# HenHouseControlleri2cfix.net
KiCad netlist of a schematic drawn in EAGLE
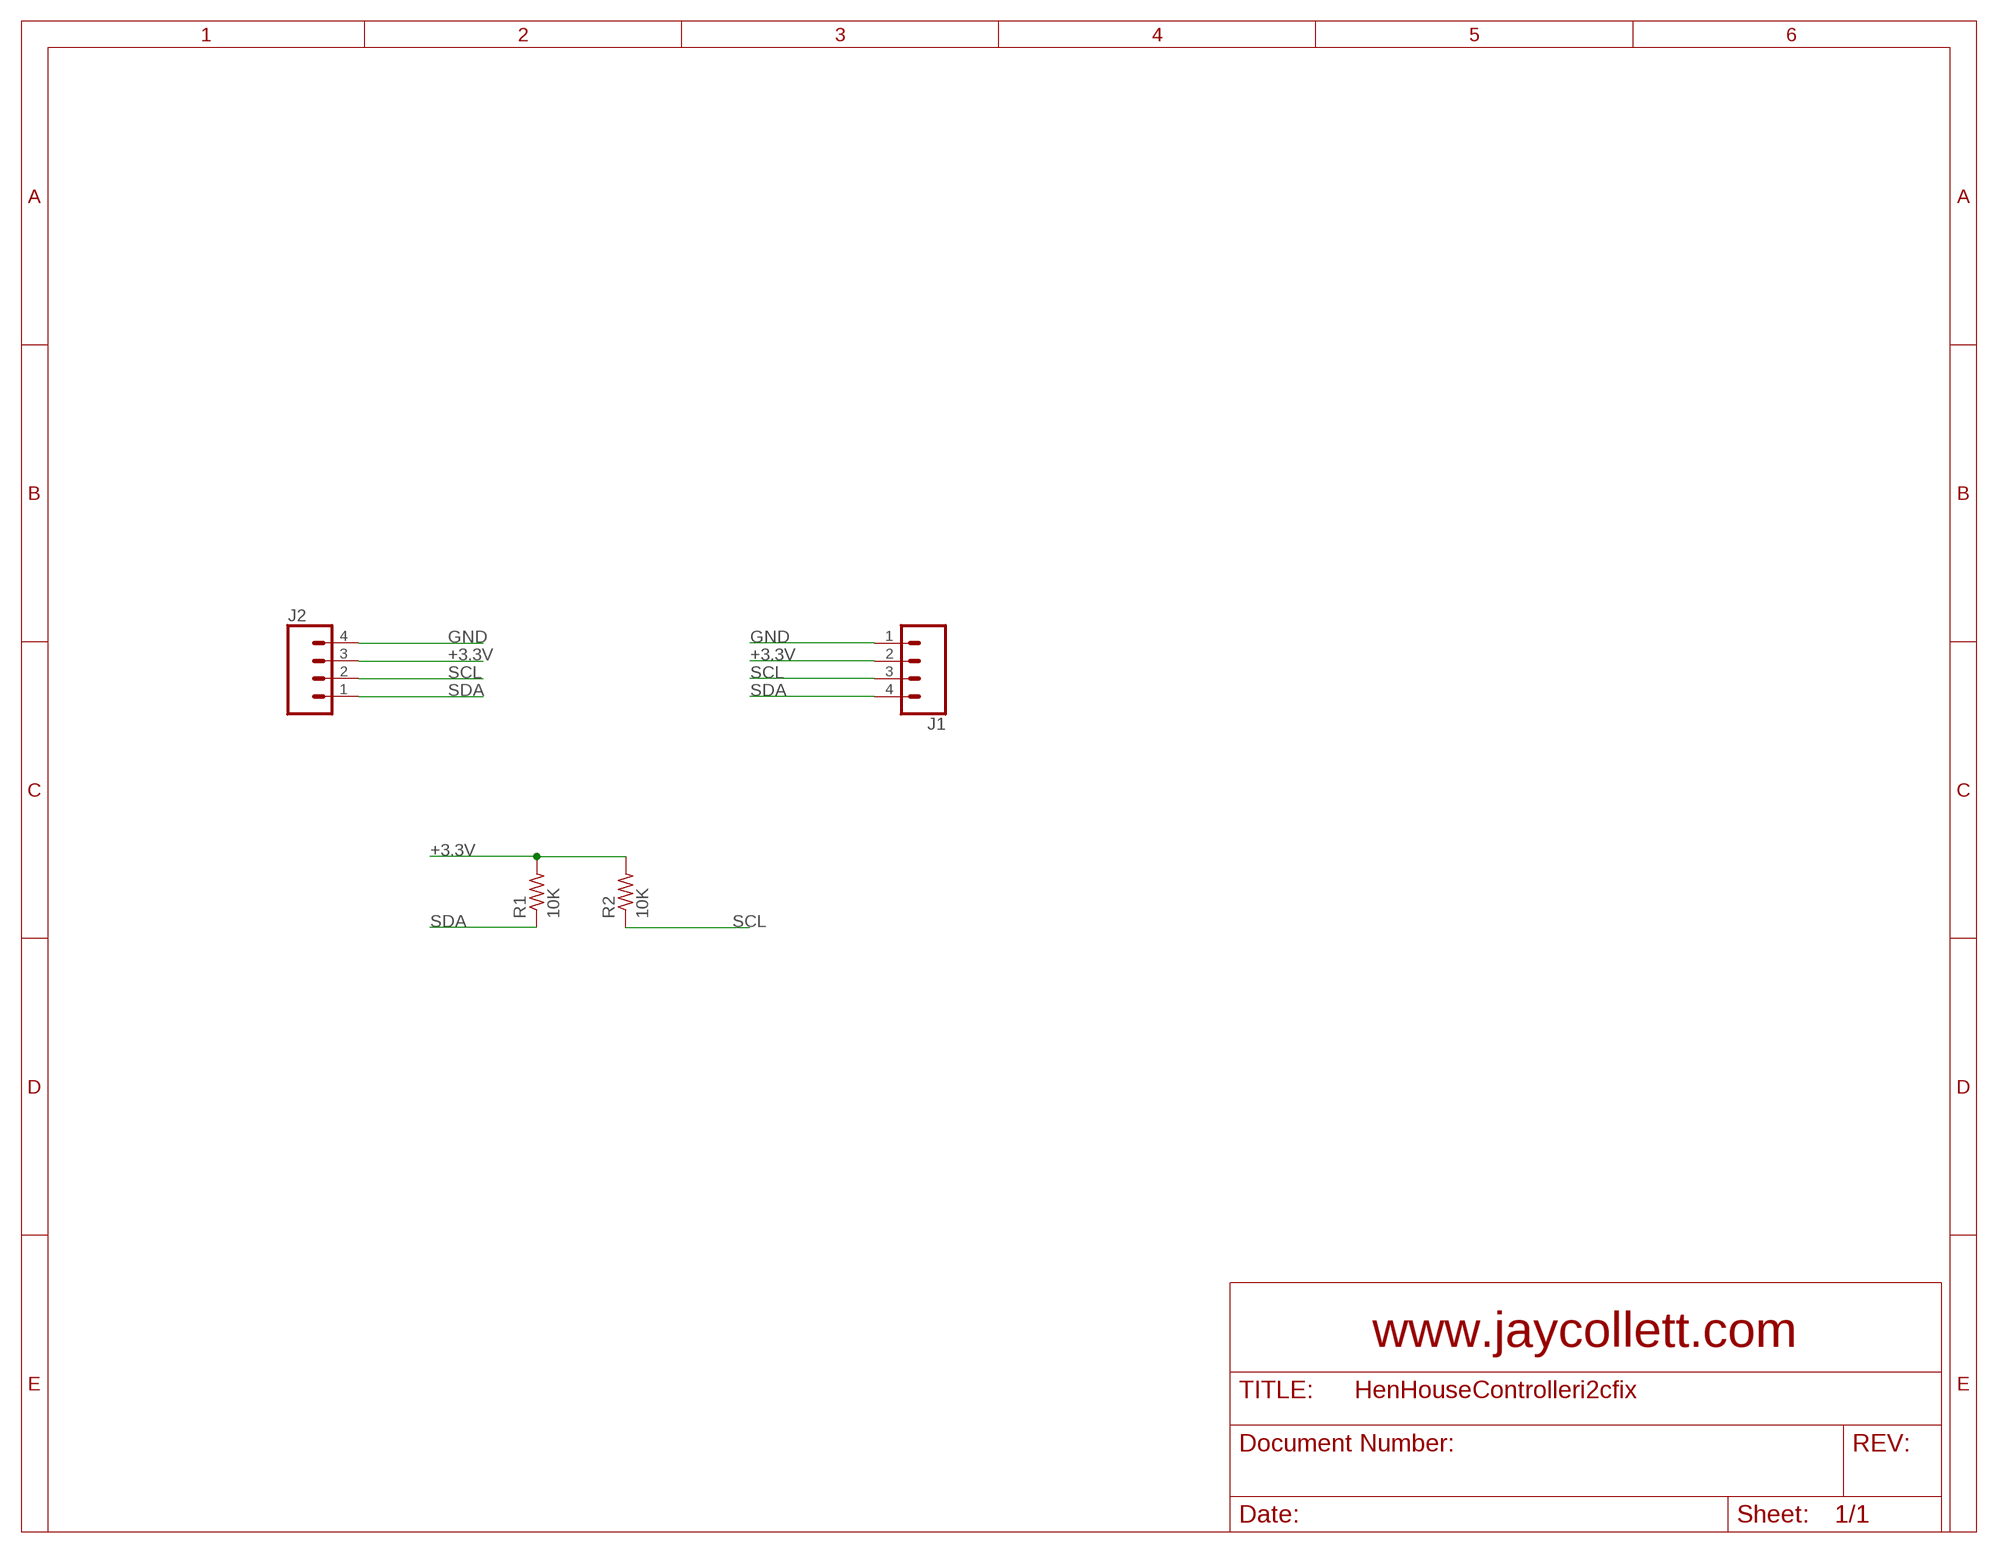
[diagram p0: schematic, sheet 1]

(export (version "E")
  (design (tool "Eeschema 10.0.6"))
  (components
    (comp (ref "J1")
      (value "CONN_04LONGPADS")
      (footprint "eagle-import:1X04_LONGPADS")
      (libsource (lib "eagle-import") (part "CONN_04LONGPADS"))
    )
    (comp (ref "J2")
      (value "CONN_04LONGPADS")
      (footprint "eagle-import:1X04_LONGPADS")
      (libsource (lib "eagle-import") (part "CONN_04LONGPADS"))
    )
    (comp (ref "R1")
      (value "10K")
      (footprint "eagle-import:R0805")
      (libsource (lib "eagle-import") (part "R-US_R0805"))
    )
    (comp (ref "R2")
      (value "10K")
      (footprint "eagle-import:R0805")
      (libsource (lib "eagle-import") (part "R-US_R0805"))
    )
  )
  (nets
    (net (code "1") (name "/+3.3V") (class "Default")
      (node (ref "J1") (pin "2") (pinfunction "2_2") (pintype "passive"))
      (node (ref "J2") (pin "3") (pinfunction "3_3") (pintype "passive"))
      (node (ref "R1") (pin "2") (pinfunction "2_2") (pintype "passive"))
      (node (ref "R2") (pin "2") (pinfunction "2_2") (pintype "passive"))
    )
    (net (code "2") (name "/GND") (class "Default")
      (node (ref "J1") (pin "1") (pinfunction "1_1") (pintype "passive"))
      (node (ref "J2") (pin "4") (pinfunction "4_4") (pintype "passive"))
    )
    (net (code "3") (name "/SCL") (class "Default")
      (node (ref "J1") (pin "3") (pinfunction "3_3") (pintype "passive"))
      (node (ref "J2") (pin "2") (pinfunction "2_2") (pintype "passive"))
      (node (ref "R2") (pin "1") (pinfunction "1_1") (pintype "passive"))
    )
    (net (code "4") (name "/SDA") (class "Default")
      (node (ref "J1") (pin "4") (pinfunction "4_4") (pintype "passive"))
      (node (ref "J2") (pin "1") (pinfunction "1_1") (pintype "passive"))
      (node (ref "R1") (pin "1") (pinfunction "1_1") (pintype "passive"))
    )
  )
)
